# MCU_F401RE.net
KiCad netlist of a schematic drawn in Altium Designer
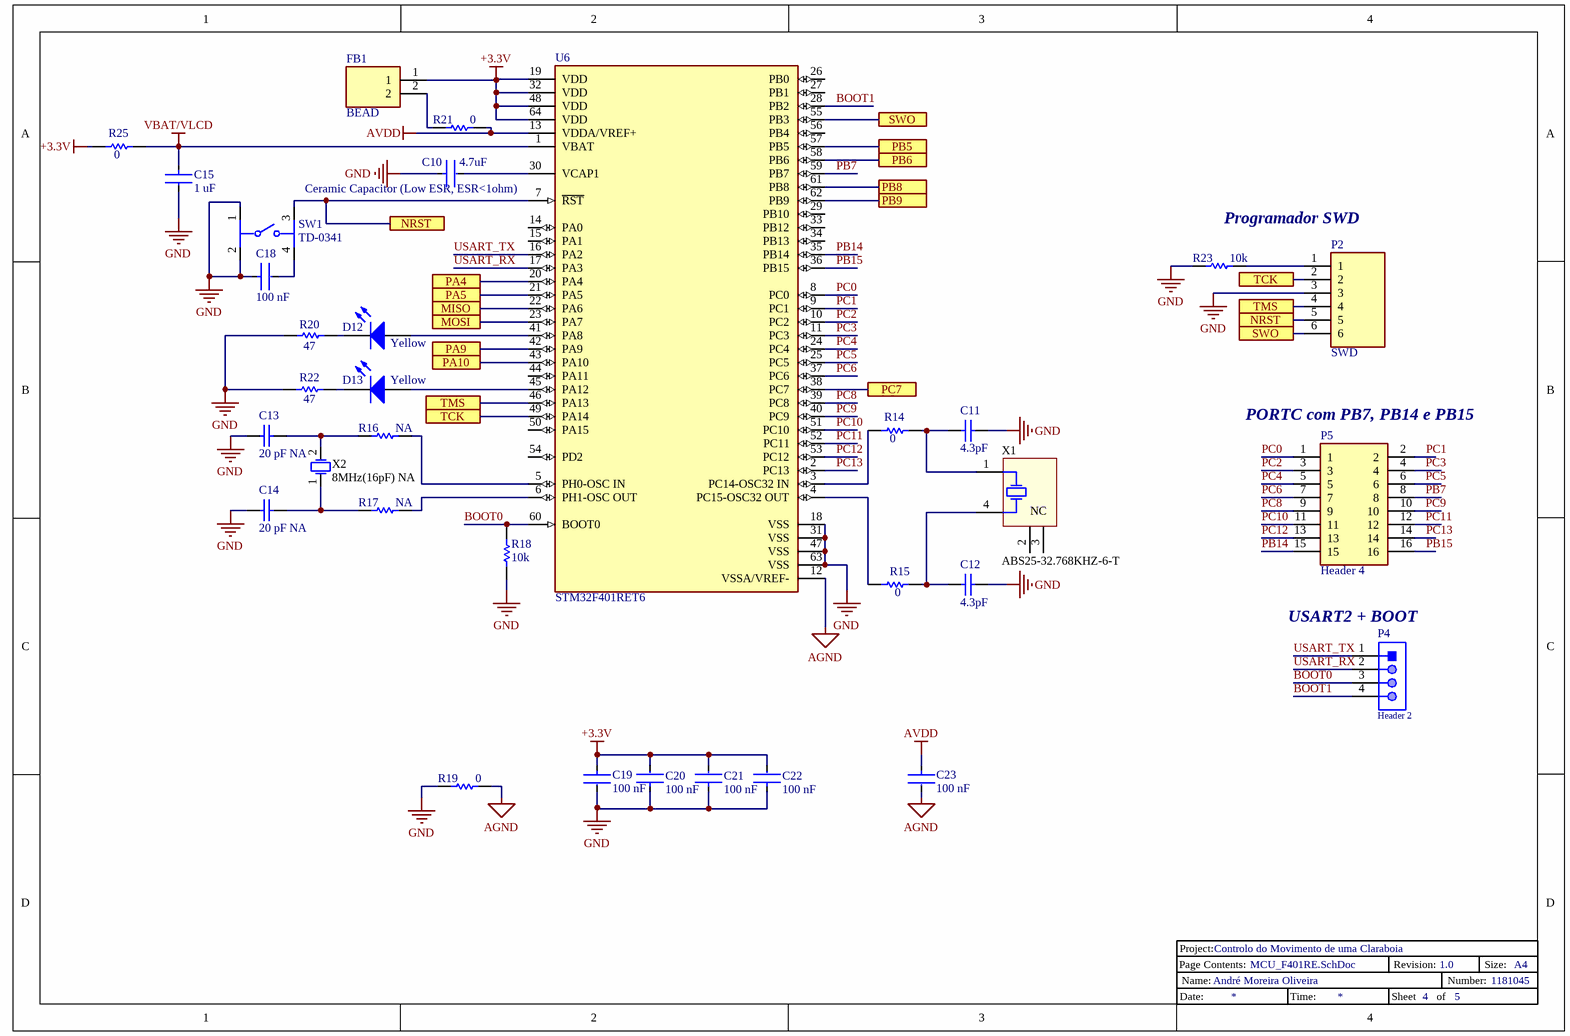
[diagram p0: MCU_F401RE.SchDoc]

(export (version "E")
  (design (tool "Eeschema 10.0.6"))
  (components
    (comp (ref "C10")
      (value "4.7uF")
      (footprint "FP-GRT21B-0_15-IPC_B")
      (description "Cap Ceramic 4.7uF 50V X5R ±10% SMD 0805 +85°C Emboss T/R")
      (fields (field (name "TOLERANCE") "10%"))
      (libsource (lib "Altium Content Vault") (part "11868f565c42a9108669ba33697ecf6"))
    )
    (comp (ref "C11")
      (value "4.3pF")
      (footprint "CAPC1608X90X35LL10T15")
      (description "0603")
      (fields (field (name "PART NUMBER") "GQM1885C2A4R3BB01D") (field (name "MANUFACTURER") "Murata"))
      (libsource (lib "Altium Content Vault") (part "CAP"))
    )
    (comp (ref "C12")
      (value "4.3pF")
      (footprint "CAPC1608X90X35LL10T15")
      (description "0603")
      (fields (field (name "PART NUMBER") "GQM1885C2A4R3BB01D") (field (name "MANUFACTURER") "Murata"))
      (libsource (lib "Altium Content Vault") (part "CAP"))
    )
    (comp (ref "C13")
      (value "20 pF NA")
      (footprint "CAPC1608X90X35NL15T15")
      (fields
        (field (name "PART NUMBER") "06035A200JAT2A")
        (field (name "MANUFACTURER") "AVX Interconnect / Elco")
      )
      (libsource (lib "Altium Content Vault") (part "CAP"))
    )
    (comp (ref "C14")
      (value "20 pF NA")
      (footprint "CAPC1608X90X35NL15T15")
      (fields
        (field (name "PART NUMBER") "06035A200JAT2A")
        (field (name "MANUFACTURER") "AVX Interconnect / Elco")
      )
      (libsource (lib "Altium Content Vault") (part "CAP"))
    )
    (comp (ref "C15")
      (value "1 uF")
      (footprint "FP-CC0603-DA-MFG")
      (description "CAP CER 1UF 16V X5R 0603")
      (fields
        (field (name "OCTOPART") "https://octopart.com/cc0603krx5r7bb105-yageo-8376530")
        (field (name "MANUFACTURER PART NUMBER") "CC0603KRX5R7BB105")
      )
      (libsource (lib "Altium Content Vault") (part "11868f565c42a9108669ba33697ecf6"))
    )
    (comp (ref "C18")
      (value "100 nF")
      (footprint "FP-CC0603-DA-MFG")
      (description "CAP CER 0.1UF 50V X7R 0603")
      (fields (field (name "MANUFACTURER") "YAGEO") (field (name "VOLTAGE") "50 V"))
      (libsource (lib "Altium Content Vault") (part "11868f565c42a9108669ba33697ecf6"))
    )
    (comp (ref "C19")
      (value "100 nF")
      (footprint "FP-CC0603-DA-MFG")
      (description "CAP CER 0.1UF 50V X7R 0603")
      (fields (field (name "MANUFACTURER") "YAGEO") (field (name "VOLTAGE") "50 V"))
      (libsource (lib "Altium Content Vault") (part "11868f565c42a9108669ba33697ecf6"))
    )
    (comp (ref "C20")
      (value "100 nF")
      (footprint "FP-CC0603-DA-MFG")
      (description "CAP CER 0.1UF 50V X7R 0603")
      (fields (field (name "MANUFACTURER") "YAGEO") (field (name "VOLTAGE") "50 V"))
      (libsource (lib "Altium Content Vault") (part "11868f565c42a9108669ba33697ecf6"))
    )
    (comp (ref "C21")
      (value "100 nF")
      (footprint "FP-CC0603-DA-MFG")
      (description "CAP CER 0.1UF 50V X7R 0603")
      (fields (field (name "MANUFACTURER") "YAGEO") (field (name "VOLTAGE") "50 V"))
      (libsource (lib "Altium Content Vault") (part "11868f565c42a9108669ba33697ecf6"))
    )
    (comp (ref "C22")
      (value "100 nF")
      (footprint "FP-CC0603-DA-MFG")
      (description "CAP CER 0.1UF 50V X7R 0603")
      (fields (field (name "MANUFACTURER") "YAGEO") (field (name "VOLTAGE") "50 V"))
      (libsource (lib "Altium Content Vault") (part "11868f565c42a9108669ba33697ecf6"))
    )
    (comp (ref "C23")
      (value "100 nF")
      (footprint "FP-CC0603-DA-MFG")
      (description "CAP CER 0.1UF 50V X7R 0603")
      (fields (field (name "MANUFACTURER") "YAGEO") (field (name "VOLTAGE") "50 V"))
      (libsource (lib "Altium Content Vault") (part "11868f565c42a9108669ba33697ecf6"))
    )
    (comp (ref "D12")
      (value "Yellow")
      (footprint "0805_A")
      (description "SMD mono-color Chip LED, WL-SMCW, Yellow")
      (fields (field (name "MANUFACTURER") "Wuerth Elektronik") (field (name "PARTNUMBER") "150080YS75000"))
      (libsource (lib "Altium Content Vault") (part "WE-LED_K1A2-2"))
    )
    (comp (ref "D13")
      (value "Yellow")
      (footprint "0805_A")
      (description "SMD mono-color Chip LED, WL-SMCW, Yellow")
      (fields (field (name "MANUFACTURER") "Wuerth Elektronik") (field (name "PARTNUMBER") "150080YS75000"))
      (libsource (lib "Altium Content Vault") (part "WE-LED_K1A2-2"))
    )
    (comp (ref "FB1")
      (value "BEAD")
      (footprint "SamacSys:BEADC1608X95N")
      (description "Ferrite Bead")
      (fields
        (field (name "MANUFACTURER_PART_NUMBER") "MMZ1608S601ATD25")
        (field (name "MOUSER PART NUMBER") "810-MMZ1608S601ATD25")
      )
      (libsource (lib "*") (part "MMZ1608S601ATD25"))
    )
    (comp (ref "P2")
      (value "SWD")
      (footprint "SamacSys:HDRV6W30P0X127_1X6_762X210X430P")
      (description "Connector")
      (fields
        (field (name "MANUFACTURER_PART_NUMBER") "M50-3530642")
        (field (name "MOUSER PART NUMBER") "855-M50-3530642")
      )
      (libsource (lib "*") (part "M50-3530642"))
    )
    (comp (ref "P4")
      (value "Header 2")
      (footprint "61300411121")
      (description "THT Vertical Pin Header WR-PHD, Pitch 2.54 mm, Single Row, 4 pins")
      (fields
        (field (name "MANUFACTURER") "Wurth Elektronik")
        (field (name "PART NUMBER") "61300411121")
        (field (name "PUBLISHER") "WurthElektronik")
      )
      (libsource (lib "Altium Content Vault") (part "WE-CN-1P-M-R4"))
    )
    (comp (ref "P5")
      (value "Header 4")
      (footprint "SamacSys:HDRV16W67P254_2X8_1991X488X821P")
      (description "Connector")
      (fields
        (field (name "MANUFACTURER_PART_NUMBER") "5-146254-8")
        (field (name "MOUSER PART NUMBER") "571-5-146254-8")
      )
      (libsource (lib "*") (part "5-146254-8"))
    )
    (comp (ref "R14")
      (value "0")
      (footprint "RESC1608X55X25ML10T15")
      (description "Chip Resistor, 0 Ohm, +/- 5%, 0.1 W, -55 to 155 degC, 0603 (1608 Metric), RoHS, Tape and Reel")
      (fields (field (name "TOLERANCE") "5%") (field (name "MANUFACTURER") "Yageo"))
      (libsource (lib "Altium Content Vault") (part "RES-2"))
    )
    (comp (ref "R15")
      (value "0")
      (footprint "RESC1608X55X25ML10T15")
      (description "Chip Resistor, 0 Ohm, +/- 5%, 0.1 W, -55 to 155 degC, 0603 (1608 Metric), RoHS, Tape and Reel")
      (fields (field (name "TOLERANCE") "5%") (field (name "MANUFACTURER") "Yageo"))
      (libsource (lib "Altium Content Vault") (part "RES-2"))
    )
    (comp (ref "R16")
      (value "NA")
      (footprint "RESC1608X55X25ML10T15")
      (description "Chip Resistor, 0 Ohm, +/- 5%, 0.1 W, -55 to 155 degC, 0603 (1608 Metric), RoHS, Tape and Reel")
      (fields (field (name "TOLERANCE") "5%") (field (name "MANUFACTURER") "Yageo"))
      (libsource (lib "Altium Content Vault") (part "RES-2"))
    )
    (comp (ref "R17")
      (value "NA")
      (footprint "RESC1608X55X25ML10T15")
      (description "Chip Resistor, 0 Ohm, +/- 5%, 0.1 W, -55 to 155 degC, 0603 (1608 Metric), RoHS, Tape and Reel")
      (fields (field (name "TOLERANCE") "5%") (field (name "MANUFACTURER") "Yageo"))
      (libsource (lib "Altium Content Vault") (part "RES-2"))
    )
    (comp (ref "R18")
      (value "10k")
      (footprint "RESC1608X55X25ML10T15")
      (description "Resistor, 10 kOhm, +/- 5%, 100 mW, -55 to 155 degC, 0603 (1608 Metric), RoHS, Tape and Reel")
      (fields (field (name "MANUFACTURER") "Yageo") (field (name "TOLERANCE") "5%"))
      (libsource (lib "Altium Content Vault") (part "RES-2"))
    )
    (comp (ref "R19")
      (value "0")
      (footprint "RESC1608X55X25ML10T15")
      (description "Chip Resistor, 0 Ohm, +/- 5%, 0.1 W, -55 to 155 degC, 0603 (1608 Metric), RoHS, Tape and Reel")
      (fields (field (name "TOLERANCE") "5%") (field (name "MANUFACTURER") "Yageo"))
      (libsource (lib "Altium Content Vault") (part "RES-2"))
    )
    (comp (ref "R20")
      (value "47")
      (footprint "RESC1608X55X30NL20T20")
      (fields (field (name "PART NUMBER") "ERA3AEB470V") (field (name "MANUFACTURER") "Panasonic"))
      (libsource (lib "Altium Content Vault") (part "RES"))
    )
    (comp (ref "R21")
      (value "0")
      (footprint "RESC1608X55X25ML10T15")
      (description "Chip Resistor, 0 Ohm, +/- 5%, 0.1 W, -55 to 155 degC, 0603 (1608 Metric), RoHS, Tape and Reel")
      (fields (field (name "TOLERANCE") "5%") (field (name "MANUFACTURER") "Yageo"))
      (libsource (lib "Altium Content Vault") (part "RES-2"))
    )
    (comp (ref "R22")
      (value "47")
      (footprint "RESC1608X55X30NL20T20")
      (fields (field (name "PART NUMBER") "ERA3AEB470V") (field (name "MANUFACTURER") "Panasonic"))
      (libsource (lib "Altium Content Vault") (part "RES"))
    )
    (comp (ref "R23")
      (value "10k")
      (footprint "RESC1608X55X25ML10T15")
      (description "Resistor, 10 kOhm, +/- 5%, 100 mW, -55 to 155 degC, 0603 (1608 Metric), RoHS, Tape and Reel")
      (fields (field (name "MANUFACTURER") "Yageo") (field (name "TOLERANCE") "5%"))
      (libsource (lib "") (part "RES-2_1"))
    )
    (comp (ref "R25")
      (value "0")
      (footprint "RESC1608X55X25ML10T15")
      (description "Chip Resistor, 0 Ohm, +/- 5%, 0.1 W, -55 to 155 degC, 0603 (1608 Metric), RoHS, Tape and Reel")
      (fields (field (name "TOLERANCE") "5%") (field (name "MANUFACTURER") "Yageo"))
      (libsource (lib "Altium Content Vault") (part "RES-2"))
    )
    (comp (ref "SW1")
      (value "TD-0341")
      (footprint "FP-1571563-9-MFG")
      (description "SWITCH TACTILE SPST-NO 0.05A 24V")
      (fields
        (field (name "MANUFACTURER") "TE Connectivity")
        (field (name "MANUFACTURER PART NUMBER") "1571563-9")
      )
      (libsource (lib "Altium Content Vault") (part "b8895f3f4cefb76e1819d2863dba89b"))
    )
    (comp (ref "Title_Block_4") (value "Title_Block") (libsource (lib "Title_Block") (part "Title_Block")))
    (comp (ref "U6")
      (value "STM32F401RET6")
      (footprint "FP-LQFP64-5W-MFG")
      (description "IC MCU 32BIT 512KB FLASH 64LQFP")
      (fields
        (field (name "OCTOPART") "https://octopart.com/stm32f401ret6-stmicroelectronics-34185993")
        (field (name "MANUFACTURER") "STMicroelectronics")
      )
      (libsource (lib "Altium Content Vault") (part "7f49e7cdc56bbeda8d86db7d775c506"))
    )
    (comp (ref "X1")
      (value "ABS25-32.768KHZ-6-T")
      (footprint "ABRA-ABS25-4_V")
      (fields (field (name "TOLERANCE") "20PPM") (field (name "MANUFACTURER") "Abracon"))
      (libsource (lib "Altium Content Vault") (part "ABRA-XTAL_1-4-4"))
    )
    (comp (ref "X2")
      (value "8MHz(16pF) NA")
      (footprint "FOX-FOXSLF160-20")
      (description "Resistance Weld Thru-Hole Crystal, 16 MHz, -20 to 70 degC, 2-Pin THD, RoHS, Bulk")
      (fields (field (name "TOLERANCE") "1%"))
      (libsource (lib "Altium Content Vault") (part "XTAL-1-2-2"))
    )
  )
  (nets
    (net (code "1") (name "+3.3V") (class "Default")
      (node (ref "C19") (pin "1") (pinfunction "1_1") (pintype "passive"))
      (node (ref "C20") (pin "2") (pinfunction "2_2") (pintype "passive"))
      (node (ref "C21") (pin "2") (pinfunction "2_2") (pintype "passive"))
      (node (ref "C22") (pin "2") (pinfunction "2_2") (pintype "passive"))
      (node (ref "FB1") (pin "1") (pinfunction "1_1") (pintype "passive"))
      (node (ref "R25") (pin "1") (pinfunction "1_1") (pintype "passive"))
      (node (ref "U6") (pin "19") (pinfunction "VDD_19") (pintype "power_in"))
      (node (ref "U6") (pin "32") (pinfunction "VDD_32") (pintype "power_in"))
      (node (ref "U6") (pin "48") (pinfunction "VDD_48") (pintype "power_in"))
      (node (ref "U6") (pin "64") (pinfunction "VDD_64") (pintype "power_in"))
    )
    (net (code "2") (name "/BOOT0") (class "Default")
      (node (ref "P4") (pin "3") (pinfunction "3_3") (pintype "passive"))
      (node (ref "R18") (pin "2") (pinfunction "2_2") (pintype "passive"))
      (node (ref "U6") (pin "60") (pinfunction "BOOT0_60") (pintype "input"))
    )
    (net (code "3") (name "/BOOT1") (class "Default")
      (node (ref "P4") (pin "4") (pinfunction "4_4") (pintype "passive"))
      (node (ref "U6") (pin "28") (pinfunction "PB2_28") (pintype "bidirectional"))
    )
    (net (code "4") (name "/MISO") (class "Default")
      (node (ref "U6") (pin "22") (pinfunction "PA6_22") (pintype "bidirectional"))
    )
    (net (code "5") (name "/MOSI") (class "Default")
      (node (ref "U6") (pin "23") (pinfunction "PA7_23") (pintype "bidirectional"))
    )
    (net (code "6") (name "/NRST") (class "Default")
      (node (ref "P2") (pin "5") (pinfunction "5_5") (pintype "passive"))
      (node (ref "SW1") (pin "3") (pinfunction "3_3") (pintype "passive"))
      (node (ref "U6") (pin "7") (pinfunction "~{RST}_7") (pintype "input"))
    )
    (net (code "7") (name "/PA4") (class "Default")
      (node (ref "U6") (pin "20") (pinfunction "PA4_20") (pintype "bidirectional"))
    )
    (net (code "8") (name "/PA5") (class "Default")
      (node (ref "U6") (pin "21") (pinfunction "PA5_21") (pintype "bidirectional"))
    )
    (net (code "9") (name "/PA9") (class "Default")
      (node (ref "U6") (pin "42") (pinfunction "PA9_42") (pintype "bidirectional"))
    )
    (net (code "10") (name "/PA10") (class "Default")
      (node (ref "U6") (pin "43") (pinfunction "PA10_43") (pintype "bidirectional"))
    )
    (net (code "11") (name "/PB5") (class "Default")
      (node (ref "U6") (pin "57") (pinfunction "PB5_57") (pintype "bidirectional"))
    )
    (net (code "12") (name "/PB6") (class "Default")
      (node (ref "U6") (pin "58") (pinfunction "PB6_58") (pintype "bidirectional"))
    )
    (net (code "13") (name "/PB7") (class "Default")
      (node (ref "P5") (pin "8") (pinfunction "8_8") (pintype "passive"))
      (node (ref "U6") (pin "59") (pinfunction "PB7_59") (pintype "bidirectional"))
    )
    (net (code "14") (name "/PB8") (class "Default")
      (node (ref "U6") (pin "61") (pinfunction "PB8_61") (pintype "bidirectional"))
    )
    (net (code "15") (name "/PB9") (class "Default")
      (node (ref "U6") (pin "62") (pinfunction "PB9_62") (pintype "bidirectional"))
    )
    (net (code "16") (name "/PB14") (class "Default")
      (node (ref "P5") (pin "15") (pinfunction "15_15") (pintype "passive"))
      (node (ref "U6") (pin "35") (pinfunction "PB14_35") (pintype "bidirectional"))
    )
    (net (code "17") (name "/PB15") (class "Default")
      (node (ref "P5") (pin "16") (pinfunction "16_16") (pintype "passive"))
      (node (ref "U6") (pin "36") (pinfunction "PB15_36") (pintype "bidirectional"))
    )
    (net (code "18") (name "/PC0") (class "Default")
      (node (ref "P5") (pin "1") (pinfunction "1_1") (pintype "passive"))
      (node (ref "U6") (pin "8") (pinfunction "PC0_8") (pintype "bidirectional"))
    )
    (net (code "19") (name "/PC1") (class "Default")
      (node (ref "P5") (pin "2") (pinfunction "2_2") (pintype "passive"))
      (node (ref "U6") (pin "9") (pinfunction "PC1_9") (pintype "bidirectional"))
    )
    (net (code "20") (name "/PC2") (class "Default")
      (node (ref "P5") (pin "3") (pinfunction "3_3") (pintype "passive"))
      (node (ref "U6") (pin "10") (pinfunction "PC2_10") (pintype "bidirectional"))
    )
    (net (code "21") (name "/PC3") (class "Default")
      (node (ref "P5") (pin "4") (pinfunction "4_4") (pintype "passive"))
      (node (ref "U6") (pin "11") (pinfunction "PC3_11") (pintype "bidirectional"))
    )
    (net (code "22") (name "/PC4") (class "Default")
      (node (ref "P5") (pin "5") (pinfunction "5_5") (pintype "passive"))
      (node (ref "U6") (pin "24") (pinfunction "PC4_24") (pintype "bidirectional"))
    )
    (net (code "23") (name "/PC5") (class "Default")
      (node (ref "P5") (pin "6") (pinfunction "6_6") (pintype "passive"))
      (node (ref "U6") (pin "25") (pinfunction "PC5_25") (pintype "bidirectional"))
    )
    (net (code "24") (name "/PC6") (class "Default")
      (node (ref "P5") (pin "7") (pinfunction "7_7") (pintype "passive"))
      (node (ref "U6") (pin "37") (pinfunction "PC6_37") (pintype "bidirectional"))
    )
    (net (code "25") (name "/PC7") (class "Default")
      (node (ref "U6") (pin "38") (pinfunction "PC7_38") (pintype "bidirectional"))
    )
    (net (code "26") (name "/PC8") (class "Default")
      (node (ref "P5") (pin "9") (pinfunction "9_9") (pintype "passive"))
      (node (ref "U6") (pin "39") (pinfunction "PC8_39") (pintype "bidirectional"))
    )
    (net (code "27") (name "/PC9") (class "Default")
      (node (ref "P5") (pin "10") (pinfunction "10_10") (pintype "passive"))
      (node (ref "U6") (pin "40") (pinfunction "PC9_40") (pintype "bidirectional"))
    )
    (net (code "28") (name "/PC10") (class "Default")
      (node (ref "P5") (pin "11") (pinfunction "11_11") (pintype "passive"))
      (node (ref "U6") (pin "51") (pinfunction "PC10_51") (pintype "bidirectional"))
    )
    (net (code "29") (name "/PC11") (class "Default")
      (node (ref "P5") (pin "12") (pinfunction "12_12") (pintype "passive"))
      (node (ref "U6") (pin "52") (pinfunction "PC11_52") (pintype "bidirectional"))
    )
    (net (code "30") (name "/PC12") (class "Default")
      (node (ref "P5") (pin "13") (pinfunction "13_13") (pintype "passive"))
      (node (ref "U6") (pin "53") (pinfunction "PC12_53") (pintype "bidirectional"))
    )
    (net (code "31") (name "/PC13") (class "Default")
      (node (ref "P5") (pin "14") (pinfunction "14_14") (pintype "passive"))
      (node (ref "U6") (pin "2") (pinfunction "PC13_2") (pintype "bidirectional"))
    )
    (net (code "32") (name "/SWO") (class "Default")
      (node (ref "P2") (pin "6") (pinfunction "6_6") (pintype "passive"))
      (node (ref "U6") (pin "55") (pinfunction "PB3_55") (pintype "bidirectional"))
    )
    (net (code "33") (name "/TCK") (class "Default")
      (node (ref "P2") (pin "2") (pinfunction "2_2") (pintype "passive"))
      (node (ref "U6") (pin "49") (pinfunction "PA14_49") (pintype "bidirectional"))
    )
    (net (code "34") (name "/TMS") (class "Default")
      (node (ref "P2") (pin "4") (pinfunction "4_4") (pintype "passive"))
      (node (ref "U6") (pin "46") (pinfunction "PA13_46") (pintype "bidirectional"))
    )
    (net (code "35") (name "/USART_RX") (class "Default")
      (node (ref "P4") (pin "2") (pinfunction "2_2") (pintype "passive"))
      (node (ref "U6") (pin "17") (pinfunction "PA3_17") (pintype "bidirectional"))
    )
    (net (code "36") (name "/USART_TX") (class "Default")
      (node (ref "P4") (pin "1") (pinfunction "1_1") (pintype "passive"))
      (node (ref "U6") (pin "16") (pinfunction "PA2_16") (pintype "bidirectional"))
    )
    (net (code "37") (name "AGND") (class "Default")
      (node (ref "C23") (pin "2") (pinfunction "2_2") (pintype "passive"))
      (node (ref "R19") (pin "2") (pinfunction "2_2") (pintype "passive"))
      (node (ref "U6") (pin "12") (pinfunction "VSSA/VREF-_12") (pintype "power_in"))
    )
    (net (code "38") (name "AVDD") (class "Default")
      (node (ref "C23") (pin "1") (pinfunction "1_1") (pintype "passive"))
      (node (ref "R21") (pin "2") (pinfunction "2_2") (pintype "passive"))
      (node (ref "U6") (pin "13") (pinfunction "VDDA/VREF+_13") (pintype "power_in"))
    )
    (net (code "39") (name "GND") (class "Default")
      (node (ref "C10") (pin "1") (pinfunction "1_1") (pintype "passive"))
      (node (ref "C11") (pin "2") (pinfunction "2_2") (pintype "passive"))
      (node (ref "C12") (pin "2") (pinfunction "2_2") (pintype "passive"))
      (node (ref "C13") (pin "1") (pinfunction "1_1") (pintype "passive"))
      (node (ref "C14") (pin "1") (pinfunction "1_1") (pintype "passive"))
      (node (ref "C15") (pin "2") (pinfunction "2_2") (pintype "passive"))
      (node (ref "C18") (pin "1") (pinfunction "1_1") (pintype "passive"))
      (node (ref "C19") (pin "2") (pinfunction "2_2") (pintype "passive"))
      (node (ref "C20") (pin "1") (pinfunction "1_1") (pintype "passive"))
      (node (ref "C21") (pin "1") (pinfunction "1_1") (pintype "passive"))
      (node (ref "C22") (pin "1") (pinfunction "1_1") (pintype "passive"))
      (node (ref "P2") (pin "3") (pinfunction "3_3") (pintype "passive"))
      (node (ref "R18") (pin "1") (pinfunction "1_1") (pintype "passive"))
      (node (ref "R19") (pin "1") (pinfunction "1_1") (pintype "passive"))
      (node (ref "R20") (pin "2") (pinfunction "2_2") (pintype "passive"))
      (node (ref "R22") (pin "2") (pinfunction "2_2") (pintype "passive"))
      (node (ref "R23") (pin "1") (pinfunction "1_1") (pintype "passive"))
      (node (ref "SW1") (pin "1") (pinfunction "1_1") (pintype "passive"))
      (node (ref "SW1") (pin "2") (pinfunction "2_2") (pintype "passive"))
      (node (ref "U6") (pin "18") (pinfunction "VSS_18") (pintype "power_in"))
      (node (ref "U6") (pin "31") (pinfunction "VSS_31") (pintype "power_in"))
      (node (ref "U6") (pin "47") (pinfunction "VSS_47") (pintype "power_in"))
      (node (ref "U6") (pin "63") (pinfunction "VSS_63") (pintype "power_in"))
    )
    (net (code "40") (name "Net-(C13-Pad2)") (class "Default")
      (node (ref "C13") (pin "2") (pinfunction "2_2") (pintype "passive"))
      (node (ref "R16") (pin "1") (pinfunction "1_1") (pintype "passive"))
      (node (ref "X2") (pin "2") (pinfunction "2_2") (pintype "passive"))
    )
    (net (code "41") (name "Net-(C14-Pad2)") (class "Default")
      (node (ref "C14") (pin "2") (pinfunction "2_2") (pintype "passive"))
      (node (ref "R17") (pin "1") (pinfunction "1_1") (pintype "passive"))
      (node (ref "X2") (pin "1") (pinfunction "1_1") (pintype "passive"))
    )
    (net (code "42") (name "Net-(C18-Pad2)") (class "Default")
      (node (ref "C18") (pin "2") (pinfunction "2_2") (pintype "passive"))
      (node (ref "SW1") (pin "4") (pinfunction "4_4") (pintype "passive"))
    )
    (net (code "43") (name "Net-(D12-A)") (class "Default")
      (node (ref "D12") (pin "2") (pinfunction "A_2") (pintype "passive"))
      (node (ref "U6") (pin "41") (pinfunction "PA8_41") (pintype "bidirectional"))
    )
    (net (code "44") (name "Net-(D12-K)") (class "Default")
      (node (ref "D12") (pin "1") (pinfunction "K_1") (pintype "passive"))
      (node (ref "R20") (pin "1") (pinfunction "1_1") (pintype "passive"))
    )
    (net (code "45") (name "Net-(D13-A)") (class "Default")
      (node (ref "D13") (pin "2") (pinfunction "A_2") (pintype "passive"))
      (node (ref "U6") (pin "45") (pinfunction "PA12_45") (pintype "bidirectional"))
    )
    (net (code "46") (name "Net-(D13-K)") (class "Default")
      (node (ref "D13") (pin "1") (pinfunction "K_1") (pintype "passive"))
      (node (ref "R22") (pin "1") (pinfunction "1_1") (pintype "passive"))
    )
    (net (code "47") (name "Net-(FB1-Pad2)") (class "Default")
      (node (ref "FB1") (pin "2") (pinfunction "2_2") (pintype "passive"))
      (node (ref "R21") (pin "1") (pinfunction "1_1") (pintype "passive"))
    )
    (net (code "48") (name "Net-(P2-Pad1)") (class "Default")
      (node (ref "P2") (pin "1") (pinfunction "1_1") (pintype "passive"))
      (node (ref "R23") (pin "2") (pinfunction "2_2") (pintype "passive"))
    )
    (net (code "49") (name "Net-(U6-PC14-OSC32_IN)") (class "Default")
      (node (ref "R14") (pin "1") (pinfunction "1_1") (pintype "passive"))
      (node (ref "U6") (pin "3") (pinfunction "PC14-OSC32_IN_3") (pintype "bidirectional"))
    )
    (net (code "50") (name "Net-(U6-PC15-OSC32_OUT)") (class "Default")
      (node (ref "R15") (pin "1") (pinfunction "1_1") (pintype "passive"))
      (node (ref "U6") (pin "4") (pinfunction "PC15-OSC32_OUT_4") (pintype "bidirectional"))
    )
    (net (code "51") (name "Net-(U6-PH0-OSC_IN)") (class "Default")
      (node (ref "R16") (pin "2") (pinfunction "2_2") (pintype "passive"))
      (node (ref "U6") (pin "5") (pinfunction "PH0-OSC_IN_5") (pintype "bidirectional"))
    )
    (net (code "52") (name "Net-(U6-PH1-OSC_OUT)") (class "Default")
      (node (ref "R17") (pin "2") (pinfunction "2_2") (pintype "passive"))
      (node (ref "U6") (pin "6") (pinfunction "PH1-OSC_OUT_6") (pintype "bidirectional"))
    )
    (net (code "53") (name "Net-(U6-VCAP1)") (class "Default")
      (node (ref "C10") (pin "2") (pinfunction "2_2") (pintype "passive"))
      (node (ref "U6") (pin "30") (pinfunction "VCAP1_30") (pintype "power_in"))
    )
    (net (code "54") (name "Net-(X1-X1)") (class "Default")
      (node (ref "C11") (pin "1") (pinfunction "1_1") (pintype "passive"))
      (node (ref "R14") (pin "2") (pinfunction "2_2") (pintype "passive"))
      (node (ref "X1") (pin "1") (pinfunction "X1_1") (pintype "passive"))
    )
    (net (code "55") (name "Net-(X1-X2)") (class "Default")
      (node (ref "C12") (pin "1") (pinfunction "1_1") (pintype "passive"))
      (node (ref "R15") (pin "2") (pinfunction "2_2") (pintype "passive"))
      (node (ref "X1") (pin "4") (pinfunction "X2_4") (pintype "passive"))
    )
    (net (code "56") (name "VBAT{slash}VLCD") (class "Default")
      (node (ref "C15") (pin "1") (pinfunction "1_1") (pintype "passive"))
      (node (ref "R25") (pin "2") (pinfunction "2_2") (pintype "passive"))
      (node (ref "U6") (pin "1") (pinfunction "VBAT_1") (pintype "power_in"))
    )
    (net (code "57") (name "unconnected-(U6-PA0-Pad14)") (class "Default")
      (node (ref "U6") (pin "14") (pinfunction "PA0_14") (pintype "bidirectional"))
    )
    (net (code "58") (name "unconnected-(U6-PA1-Pad15)") (class "Default")
      (node (ref "U6") (pin "15") (pinfunction "PA1_15") (pintype "bidirectional"))
    )
    (net (code "59") (name "unconnected-(U6-PA11-Pad44)") (class "Default")
      (node (ref "U6") (pin "44") (pinfunction "PA11_44") (pintype "bidirectional"))
    )
    (net (code "60") (name "unconnected-(U6-PA15-Pad50)") (class "Default")
      (node (ref "U6") (pin "50") (pinfunction "PA15_50") (pintype "bidirectional"))
    )
    (net (code "61") (name "unconnected-(U6-PB0-Pad26)") (class "Default")
      (node (ref "U6") (pin "26") (pinfunction "PB0_26") (pintype "bidirectional"))
    )
    (net (code "62") (name "unconnected-(U6-PB1-Pad27)") (class "Default")
      (node (ref "U6") (pin "27") (pinfunction "PB1_27") (pintype "bidirectional"))
    )
    (net (code "63") (name "unconnected-(U6-PB4-Pad56)") (class "Default")
      (node (ref "U6") (pin "56") (pinfunction "PB4_56") (pintype "bidirectional"))
    )
    (net (code "64") (name "unconnected-(U6-PB10-Pad29)") (class "Default")
      (node (ref "U6") (pin "29") (pinfunction "PB10_29") (pintype "bidirectional"))
    )
    (net (code "65") (name "unconnected-(U6-PB12-Pad33)") (class "Default")
      (node (ref "U6") (pin "33") (pinfunction "PB12_33") (pintype "bidirectional"))
    )
    (net (code "66") (name "unconnected-(U6-PB13-Pad34)") (class "Default")
      (node (ref "U6") (pin "34") (pinfunction "PB13_34") (pintype "bidirectional"))
    )
    (net (code "67") (name "unconnected-(U6-PD2-Pad54)") (class "Default")
      (node (ref "U6") (pin "54") (pinfunction "PD2_54") (pintype "bidirectional"))
    )
    (net (code "68") (name "unconnected-(X1-NC-Pad2)") (class "Default")
      (node (ref "X1") (pin "2") (pinfunction "NC_2") (pintype "passive"))
    )
    (net (code "69") (name "unconnected-(X1-NC-Pad3)") (class "Default")
      (node (ref "X1") (pin "3") (pinfunction "NC_3") (pintype "passive"))
    )
  )
)
